# ir-sensor-breakout-mk-2_1.net
KiCad netlist of a schematic drawn in EAGLE
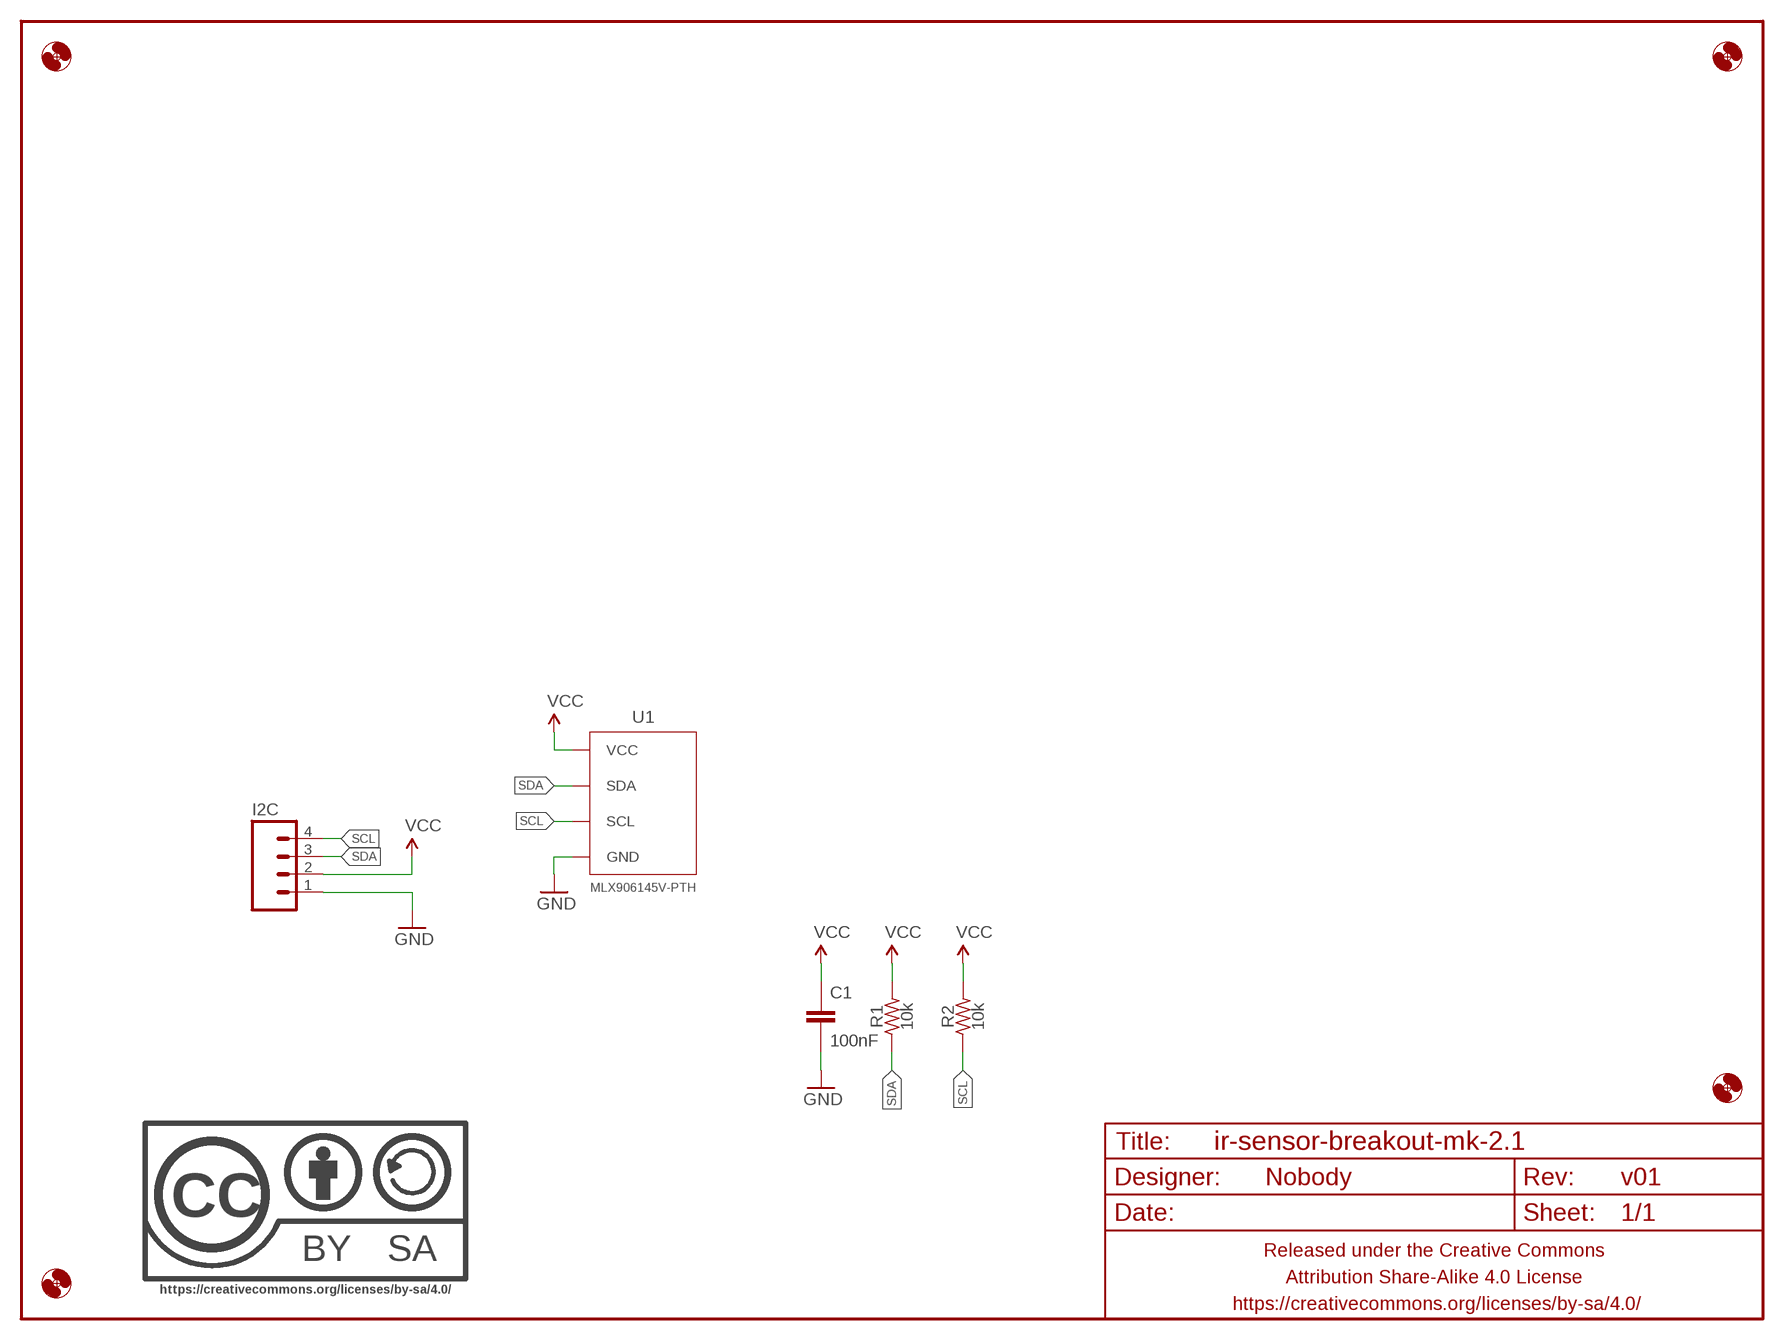
[diagram p0: schematic, sheet 1]

(export (version "E")
  (design (tool "Eeschema 10.0.6"))
  (components
    (comp (ref "C1")
      (value "100nF")
      (footprint "eagle-import:C0805")
      (libsource (lib "eagle-import") (part "CAPACITOR-CERAMICC0805"))
    )
    (comp (ref "FRAME1")
      (value "FRAME-LETTERNO_PACKAGE")
      (footprint "eagle-import:DUMMY")
      (fields (field (name "DESIGNER") "Nobody"))
      (libsource (lib "eagle-import") (part "FRAME-LETTERNO_PACKAGE"))
    )
    (comp (ref "H1")
      (value "HOLE#2")
      (footprint "eagle-import:HOLE-#2")
      (libsource (lib "eagle-import") (part "HOLE#2"))
    )
    (comp (ref "H2")
      (value "HOLE#2")
      (footprint "eagle-import:HOLE-#2")
      (libsource (lib "eagle-import") (part "HOLE#2"))
    )
    (comp (ref "H3")
      (value "HOLE#2")
      (footprint "eagle-import:HOLE-#2")
      (libsource (lib "eagle-import") (part "HOLE#2"))
    )
    (comp (ref "H4")
      (value "HOLE#2")
      (footprint "eagle-import:HOLE-#2")
      (libsource (lib "eagle-import") (part "HOLE#2"))
    )
    (comp (ref "I2C")
      (value "M04JST-PTH-VERT")
      (footprint "eagle-import:JST-4-PH-VERT-PTH")
      (libsource (lib "eagle-import") (part "M04JST-PTH-VERT"))
    )
    (comp (ref "R1")
      (value "10k")
      (footprint "eagle-import:R0805")
      (libsource (lib "eagle-import") (part "RESISTORR0805"))
    )
    (comp (ref "R2")
      (value "10k")
      (footprint "eagle-import:R0805")
      (libsource (lib "eagle-import") (part "RESISTORR0805"))
    )
    (comp (ref "U$1")
      (value "CC-BY-SA-4.0NO-URL")
      (footprint "eagle-import:CC-BY-SA-4.0-NO-URL")
      (libsource (lib "eagle-import") (part "CC-BY-SA-4.0NO-URL"))
    )
    (comp (ref "U1")
      (value "MLX906145V-PTH")
      (footprint "eagle-import:TO-39-4")
      (libsource (lib "eagle-import") (part "MLX906145V-PTH"))
    )
  )
  (nets
    (net (code "1") (name "GND") (class "Default")
      (node (ref "C1") (pin "2") (pinfunction "2_2") (pintype "passive"))
      (node (ref "I2C") (pin "1") (pinfunction "1_1") (pintype "passive"))
      (node (ref "U1") (pin "4") (pinfunction "GND_4") (pintype "bidirectional"))
    )
    (net (code "2") (name "SCL") (class "Default")
      (node (ref "I2C") (pin "4") (pinfunction "4_4") (pintype "passive"))
      (node (ref "R2") (pin "1") (pinfunction "1_1") (pintype "passive"))
      (node (ref "U1") (pin "1") (pinfunction "SCL_1") (pintype "bidirectional"))
    )
    (net (code "3") (name "SDA") (class "Default")
      (node (ref "I2C") (pin "3") (pinfunction "3_3") (pintype "passive"))
      (node (ref "R1") (pin "1") (pinfunction "1_1") (pintype "passive"))
      (node (ref "U1") (pin "2") (pinfunction "SDA_2") (pintype "bidirectional"))
    )
    (net (code "4") (name "VCC") (class "Default")
      (node (ref "C1") (pin "1") (pinfunction "1_1") (pintype "passive"))
      (node (ref "I2C") (pin "2") (pinfunction "2_2") (pintype "passive"))
      (node (ref "R1") (pin "2") (pinfunction "2_2") (pintype "passive"))
      (node (ref "R2") (pin "2") (pinfunction "2_2") (pintype "passive"))
      (node (ref "U1") (pin "3") (pinfunction "VCC_3") (pintype "bidirectional"))
    )
  )
)
